# Input_Buffer.net
KiCad netlist of a schematic drawn in Altium Designer
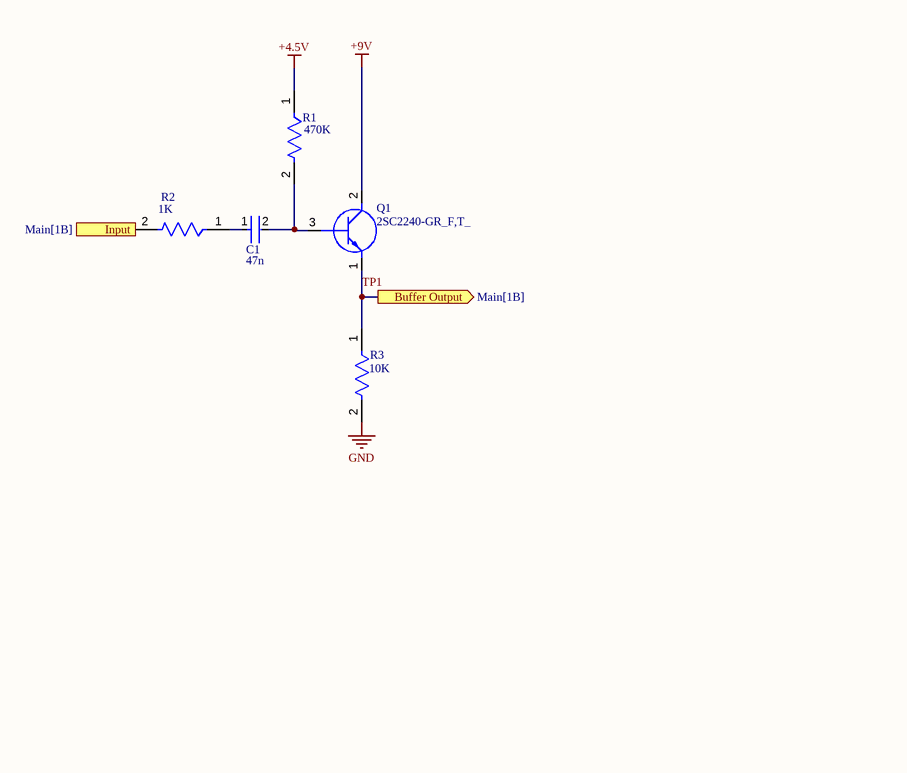
[diagram p0: Input Buffer.SchDoc]

(export (version "E")
  (design (tool "Eeschema 10.0.6"))
  (components
    (comp (ref "C1")
      (value "47n")
      (footprint "FP-RCE1A2-MFG")
      (description "Cap Ceramic 100nF 100V X7R ±10% Radial 2.5mm +125°C Automotive Bulk")
      (fields (field (name "TOLERANCE") "10%"))
      (libsource (lib "Altium Content Vault") (part "02cd4be3c70576c341d710602a673aa"))
    )
    (comp (ref "Q1")
      (value "2SC2240-GR_F,T_")
      (footprint "SamacSys:SSM3K7002CFULF")
      (description "Transistor BJT NPN")
      (fields
        (field (name "MANUFACTURER_PART_NUMBER") "2SC2240-GR(F,T)")
        (field (name "MOUSER PART NUMBER") "757-2SC2240-GRFT")
      )
      (libsource (lib "*") (part "2SC2240-GR_F,T_"))
    )
    (comp (ref "R1")
      (value "470K")
      (footprint "FP-MRS1600-MFG")
      (description "RES 20K OHM 0.4W 1% AXIAL")
      (fields (field (name "TOLERANCE") "1%"))
      (libsource (lib "Altium Content Vault") (part "1029c3af85768c4190bb7ad29bc67b5"))
    )
    (comp (ref "R2")
      (value "1K")
      (footprint "FP-MRS1600-MFG")
      (description "RES 20K OHM 0.4W 1% AXIAL")
      (fields (field (name "TOLERANCE") "1%"))
      (libsource (lib "Altium Content Vault") (part "1029c3af85768c4190bb7ad29bc67b5"))
    )
    (comp (ref "R3")
      (value "10K")
      (footprint "FP-MRS1600-MFG")
      (description "RES 20K OHM 0.4W 1% AXIAL")
      (fields (field (name "TOLERANCE") "1%"))
      (libsource (lib "Altium Content Vault") (part "1029c3af85768c4190bb7ad29bc67b5"))
    )
  )
  (nets
    (net (code "1") (name "+4.5V") (class "Default")
      (node (ref "R1") (pin "1") (pinfunction "1_1") (pintype "passive"))
    )
    (net (code "2") (name "+9V") (class "Default")
      (node (ref "Q1") (pin "2") (pinfunction "C_2") (pintype "passive"))
    )
    (net (code "3") (name "/Input") (class "Default")
      (node (ref "R2") (pin "2") (pinfunction "2_2") (pintype "passive"))
    )
    (net (code "4") (name "/TP1") (class "Default")
      (node (ref "Q1") (pin "1") (pinfunction "E_1") (pintype "passive"))
      (node (ref "R3") (pin "1") (pinfunction "1_1") (pintype "passive"))
    )
    (net (code "5") (name "GND") (class "Default")
      (node (ref "R3") (pin "2") (pinfunction "2_2") (pintype "passive"))
    )
    (net (code "6") (name "Net-(C1-Pad1)") (class "Default")
      (node (ref "C1") (pin "1") (pinfunction "1_1") (pintype "passive"))
      (node (ref "R2") (pin "1") (pinfunction "1_1") (pintype "passive"))
    )
    (net (code "7") (name "Net-(Q1-B)") (class "Default")
      (node (ref "C1") (pin "2") (pinfunction "2_2") (pintype "passive"))
      (node (ref "Q1") (pin "3") (pinfunction "B_3") (pintype "passive"))
      (node (ref "R1") (pin "2") (pinfunction "2_2") (pintype "passive"))
    )
  )
)
